# BLDC_driver.net
KiCad netlist of a schematic drawn in Altium Designer
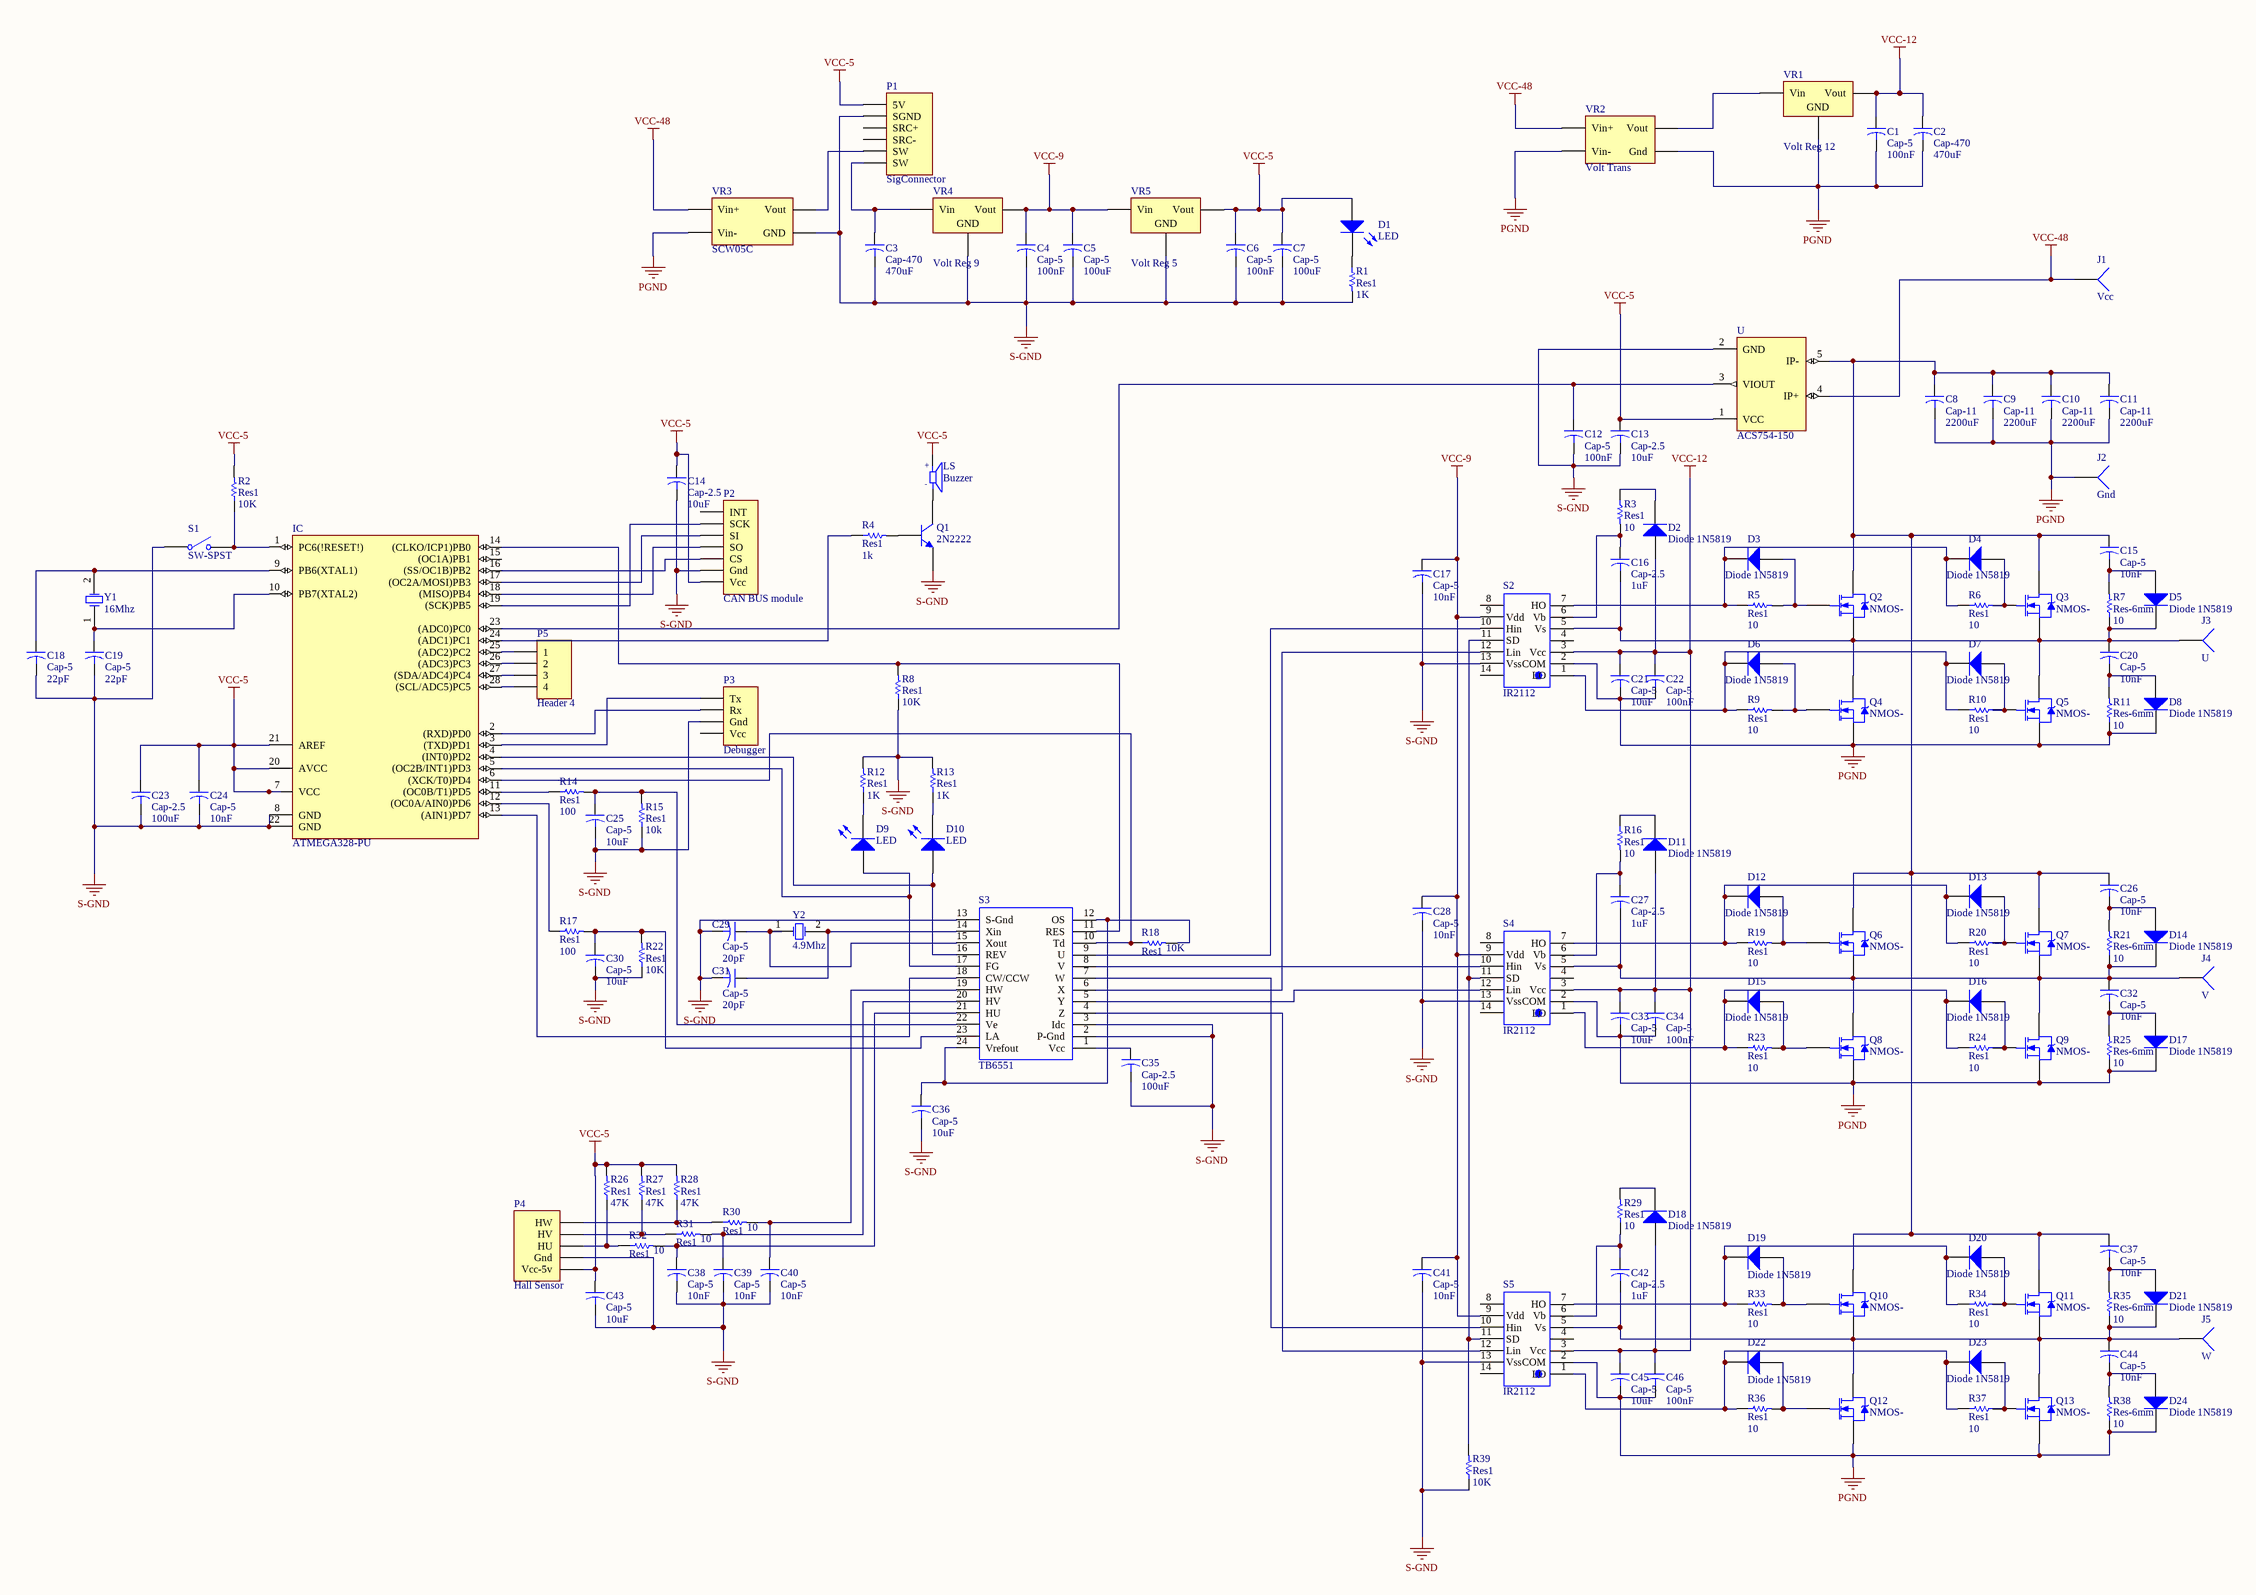
[diagram p0: BLDC_driver.SchDoc]

(export (version "E")
  (design (tool "Eeschema 10.0.6"))
  (components
    (comp (ref "C1")
      (value "Cap-5")
      (footprint "CAP-5mm")
      (description "Capacitor")
      (fields (field (name "ALTIUM_VALUE") "100nF") (field (name "PUBLISHER") "Altium Limited"))
      (libsource (lib "BLDC_driver") (part "Cap-5"))
    )
    (comp (ref "C2")
      (value "Cap-470")
      (footprint "CAP-5-470")
      (description "Capacitor")
      (fields (field (name "ALTIUM_VALUE") "470uF") (field (name "PUBLISHER") "Altium Limited"))
      (libsource (lib "BLDC_driver") (part "Cap-470"))
    )
    (comp (ref "C3")
      (value "Cap-470")
      (footprint "CAP-5-470")
      (description "Capacitor")
      (fields (field (name "ALTIUM_VALUE") "470uF") (field (name "PUBLISHER") "Altium Limited"))
      (libsource (lib "BLDC_driver") (part "Cap-470"))
    )
    (comp (ref "C4")
      (value "Cap-5")
      (footprint "CAP-5mm")
      (description "Capacitor")
      (fields (field (name "ALTIUM_VALUE") "100nF") (field (name "PUBLISHER") "Altium Limited"))
      (libsource (lib "BLDC_driver") (part "Cap-5"))
    )
    (comp (ref "C5")
      (value "Cap-5")
      (footprint "CAP-5mm")
      (description "Capacitor")
      (fields (field (name "ALTIUM_VALUE") "100uF") (field (name "PUBLISHER") "Altium Limited"))
      (libsource (lib "Miscellaneous Devices") (part "Cap-5"))
    )
    (comp (ref "C6")
      (value "Cap-5")
      (footprint "CAP-5mm")
      (description "Capacitor")
      (fields (field (name "ALTIUM_VALUE") "100nF") (field (name "PUBLISHER") "Altium Limited"))
      (libsource (lib "BLDC_driver") (part "Cap-5"))
    )
    (comp (ref "C7")
      (value "Cap-5")
      (footprint "CAP-5mm")
      (description "Capacitor")
      (fields (field (name "ALTIUM_VALUE") "100uF") (field (name "PUBLISHER") "Altium Limited"))
      (libsource (lib "Miscellaneous Devices") (part "Cap-5"))
    )
    (comp (ref "C8")
      (value "Cap-11")
      (footprint "CAP-11mm")
      (description "Capacitor")
      (fields (field (name "ALTIUM_VALUE") "2200uF") (field (name "PUBLISHER") "Altium Limited"))
      (libsource (lib "BLDC_driver") (part "Cap-11"))
    )
    (comp (ref "C9")
      (value "Cap-11")
      (footprint "CAP-11mm")
      (description "Capacitor")
      (fields (field (name "ALTIUM_VALUE") "2200uF") (field (name "PUBLISHER") "Altium Limited"))
      (libsource (lib "BLDC_driver") (part "Cap-11"))
    )
    (comp (ref "C10")
      (value "Cap-11")
      (footprint "CAP-11mm")
      (description "Capacitor")
      (fields (field (name "ALTIUM_VALUE") "2200uF") (field (name "PUBLISHER") "Altium Limited"))
      (libsource (lib "BLDC_driver") (part "Cap-11"))
    )
    (comp (ref "C11")
      (value "Cap-11")
      (footprint "CAP-11mm")
      (description "Capacitor")
      (fields (field (name "ALTIUM_VALUE") "2200uF") (field (name "PUBLISHER") "Altium Limited"))
      (libsource (lib "BLDC_driver") (part "Cap-11"))
    )
    (comp (ref "C12")
      (value "Cap-5")
      (footprint "CAP-5mm")
      (description "Capacitor")
      (fields (field (name "ALTIUM_VALUE") "100nF") (field (name "PUBLISHER") "Altium Limited"))
      (libsource (lib "BLDC_driver") (part "Cap-5"))
    )
    (comp (ref "C13")
      (value "Cap-2.5")
      (footprint "CAP-2.5mm")
      (description "Capacitor")
      (fields (field (name "ALTIUM_VALUE") "10uF") (field (name "PUBLISHER") "Altium Limited"))
      (libsource (lib "BLDC_driver") (part "Cap-2.5"))
    )
    (comp (ref "C14")
      (value "Cap-2.5")
      (footprint "CAP-2.5mm")
      (description "Capacitor")
      (fields (field (name "ALTIUM_VALUE") "10uF") (field (name "PUBLISHER") "Altium Limited"))
      (libsource (lib "BLDC_driver") (part "Cap-2.5"))
    )
    (comp (ref "C15")
      (value "Cap-5")
      (footprint "CAP-5mm")
      (description "Capacitor")
      (fields (field (name "ALTIUM_VALUE") "10nF") (field (name "PUBLISHER") "Altium Limited"))
      (libsource (lib "BLDC_driver") (part "Cap-5"))
    )
    (comp (ref "C16")
      (value "Cap-2.5")
      (footprint "CAP-2.5mm")
      (description "Capacitor")
      (fields (field (name "ALTIUM_VALUE") "1uF") (field (name "PUBLISHER") "Altium Limited"))
      (libsource (lib "BLDC_driver") (part "Cap-2.5"))
    )
    (comp (ref "C17")
      (value "Cap-5")
      (footprint "CAP-5mm")
      (description "Capacitor")
      (fields (field (name "ALTIUM_VALUE") "10nF") (field (name "PUBLISHER") "Altium Limited"))
      (libsource (lib "BLDC_driver") (part "Cap-5"))
    )
    (comp (ref "C18")
      (value "Cap-5")
      (footprint "CAP-5mm")
      (description "Capacitor")
      (fields (field (name "ALTIUM_VALUE") "22pF") (field (name "PUBLISHER") "Altium Limited"))
      (libsource (lib "BLDC_driver") (part "Cap-5"))
    )
    (comp (ref "C19")
      (value "Cap-5")
      (footprint "CAP-5mm")
      (description "Capacitor")
      (fields (field (name "ALTIUM_VALUE") "22pF") (field (name "PUBLISHER") "Altium Limited"))
      (libsource (lib "BLDC_driver") (part "Cap-5"))
    )
    (comp (ref "C20")
      (value "Cap-5")
      (footprint "CAP-5mm")
      (description "Capacitor")
      (fields (field (name "ALTIUM_VALUE") "10nF") (field (name "PUBLISHER") "Altium Limited"))
      (libsource (lib "BLDC_driver") (part "Cap-5"))
    )
    (comp (ref "C21")
      (value "Cap-5")
      (footprint "CAP-5mm")
      (description "Capacitor")
      (fields (field (name "ALTIUM_VALUE") "10uF") (field (name "PUBLISHER") "Altium Limited"))
      (libsource (lib "BLDC_driver") (part "Cap-5"))
    )
    (comp (ref "C22")
      (value "Cap-5")
      (footprint "CAP-5mm")
      (description "Capacitor")
      (fields (field (name "ALTIUM_VALUE") "100nF") (field (name "PUBLISHER") "Altium Limited"))
      (libsource (lib "BLDC_driver") (part "Cap-5"))
    )
    (comp (ref "C23")
      (value "Cap-2.5")
      (footprint "CAP-2.5mm")
      (description "Capacitor")
      (fields (field (name "ALTIUM_VALUE") "100uF") (field (name "PUBLISHER") "Altium Limited"))
      (libsource (lib "BLDC_driver") (part "Cap-2.5"))
    )
    (comp (ref "C24")
      (value "Cap-5")
      (footprint "CAP-5mm")
      (description "Capacitor")
      (fields (field (name "ALTIUM_VALUE") "10nF") (field (name "PUBLISHER") "Altium Limited"))
      (libsource (lib "BLDC_driver") (part "Cap-5"))
    )
    (comp (ref "C25")
      (value "Cap-5")
      (footprint "CAP-5mm")
      (description "Capacitor")
      (fields (field (name "ALTIUM_VALUE") "10uF") (field (name "PUBLISHER") "Altium Limited"))
      (libsource (lib "BLDC_driver") (part "Cap-5"))
    )
    (comp (ref "C26")
      (value "Cap-5")
      (footprint "CAP-5mm")
      (description "Capacitor")
      (fields (field (name "ALTIUM_VALUE") "10nF") (field (name "PUBLISHER") "Altium Limited"))
      (libsource (lib "BLDC_driver") (part "Cap-5"))
    )
    (comp (ref "C27")
      (value "Cap-2.5")
      (footprint "CAP-2.5mm")
      (description "Capacitor")
      (fields (field (name "ALTIUM_VALUE") "1uF") (field (name "PUBLISHER") "Altium Limited"))
      (libsource (lib "BLDC_driver") (part "Cap-2.5"))
    )
    (comp (ref "C28")
      (value "Cap-5")
      (footprint "CAP-5mm")
      (description "Capacitor")
      (fields (field (name "ALTIUM_VALUE") "10nF") (field (name "PUBLISHER") "Altium Limited"))
      (libsource (lib "BLDC_driver") (part "Cap-5"))
    )
    (comp (ref "C29")
      (value "Cap-5")
      (footprint "CAP-5mm")
      (description "Capacitor")
      (fields (field (name "ALTIUM_VALUE") "20pF") (field (name "PUBLISHER") "Altium Limited"))
      (libsource (lib "BLDC_driver") (part "Cap-5"))
    )
    (comp (ref "C30")
      (value "Cap-5")
      (footprint "CAP-5mm")
      (description "Capacitor")
      (fields (field (name "ALTIUM_VALUE") "10uF") (field (name "PUBLISHER") "Altium Limited"))
      (libsource (lib "BLDC_driver") (part "Cap-5"))
    )
    (comp (ref "C31")
      (value "Cap-5")
      (footprint "CAP-5mm")
      (description "Capacitor")
      (fields (field (name "ALTIUM_VALUE") "20pF") (field (name "PUBLISHER") "Altium Limited"))
      (libsource (lib "BLDC_driver") (part "Cap-5"))
    )
    (comp (ref "C32")
      (value "Cap-5")
      (footprint "CAP-5mm")
      (description "Capacitor")
      (fields (field (name "ALTIUM_VALUE") "10nF") (field (name "PUBLISHER") "Altium Limited"))
      (libsource (lib "BLDC_driver") (part "Cap-5"))
    )
    (comp (ref "C33")
      (value "Cap-5")
      (footprint "CAP-5mm")
      (description "Capacitor")
      (fields (field (name "ALTIUM_VALUE") "10uF") (field (name "PUBLISHER") "Altium Limited"))
      (libsource (lib "BLDC_driver") (part "Cap-5"))
    )
    (comp (ref "C34")
      (value "Cap-5")
      (footprint "CAP-5mm")
      (description "Capacitor")
      (fields (field (name "ALTIUM_VALUE") "100nF") (field (name "PUBLISHER") "Altium Limited"))
      (libsource (lib "BLDC_driver") (part "Cap-5"))
    )
    (comp (ref "C35")
      (value "Cap-2.5")
      (footprint "CAP-2.5mm")
      (description "Capacitor")
      (fields (field (name "ALTIUM_VALUE") "100uF") (field (name "PUBLISHER") "Altium Limited"))
      (libsource (lib "BLDC_driver") (part "Cap-2.5"))
    )
    (comp (ref "C36")
      (value "Cap-5")
      (footprint "CAP-5mm")
      (description "Capacitor")
      (fields (field (name "ALTIUM_VALUE") "10uF") (field (name "PUBLISHER") "Altium Limited"))
      (libsource (lib "BLDC_driver") (part "Cap-5"))
    )
    (comp (ref "C37")
      (value "Cap-5")
      (footprint "CAP-5mm")
      (description "Capacitor")
      (fields (field (name "ALTIUM_VALUE") "10nF") (field (name "PUBLISHER") "Altium Limited"))
      (libsource (lib "BLDC_driver") (part "Cap-5"))
    )
    (comp (ref "C38")
      (value "Cap-5")
      (footprint "CAP-5mm")
      (description "Capacitor")
      (fields (field (name "ALTIUM_VALUE") "10nF") (field (name "PUBLISHER") "Altium Limited"))
      (libsource (lib "BLDC_driver") (part "Cap-5"))
    )
    (comp (ref "C39")
      (value "Cap-5")
      (footprint "CAP-5mm")
      (description "Capacitor")
      (fields (field (name "ALTIUM_VALUE") "10nF") (field (name "PUBLISHER") "Altium Limited"))
      (libsource (lib "BLDC_driver") (part "Cap-5"))
    )
    (comp (ref "C40")
      (value "Cap-5")
      (footprint "CAP-5mm")
      (description "Capacitor")
      (fields (field (name "ALTIUM_VALUE") "10nF") (field (name "PUBLISHER") "Altium Limited"))
      (libsource (lib "BLDC_driver") (part "Cap-5"))
    )
    (comp (ref "C41")
      (value "Cap-5")
      (footprint "CAP-5mm")
      (description "Capacitor")
      (fields (field (name "ALTIUM_VALUE") "10nF") (field (name "PUBLISHER") "Altium Limited"))
      (libsource (lib "BLDC_driver") (part "Cap-5"))
    )
    (comp (ref "C42")
      (value "Cap-2.5")
      (footprint "CAP-2.5mm")
      (description "Capacitor")
      (fields (field (name "ALTIUM_VALUE") "1uF") (field (name "PUBLISHER") "Altium Limited"))
      (libsource (lib "BLDC_driver") (part "Cap-2.5"))
    )
    (comp (ref "C43")
      (value "Cap-5")
      (footprint "CAP-5mm")
      (description "Capacitor")
      (fields (field (name "ALTIUM_VALUE") "10uF") (field (name "PUBLISHER") "Altium Limited"))
      (libsource (lib "BLDC_driver") (part "Cap-5"))
    )
    (comp (ref "C44")
      (value "Cap-5")
      (footprint "CAP-5mm")
      (description "Capacitor")
      (fields (field (name "ALTIUM_VALUE") "10nF") (field (name "PUBLISHER") "Altium Limited"))
      (libsource (lib "BLDC_driver") (part "Cap-5"))
    )
    (comp (ref "C45")
      (value "Cap-5")
      (footprint "CAP-5mm")
      (description "Capacitor")
      (fields (field (name "ALTIUM_VALUE") "10uF") (field (name "PUBLISHER") "Altium Limited"))
      (libsource (lib "BLDC_driver") (part "Cap-5"))
    )
    (comp (ref "C46")
      (value "Cap-5")
      (footprint "CAP-5mm")
      (description "Capacitor")
      (fields (field (name "ALTIUM_VALUE") "100nF") (field (name "PUBLISHER") "Altium Limited"))
      (libsource (lib "BLDC_driver") (part "Cap-5"))
    )
    (comp (ref "D1")
      (value "LED")
      (footprint "LED-2.5mm")
      (description "Typical LED")
      (fields (field (name "PUBLISHER") "Altium Limited"))
      (libsource (lib "BLDC_driver") (part "LED0"))
    )
    (comp (ref "D2")
      (value "Diode 1N5819")
      (footprint "DO-5mm")
      (description "3 Amp Medium Power Silicon Rectifier Diode")
      (fields (field (name "PUBLISHER") "Altium Limited"))
      (libsource (lib "BLDC_driver") (part "Diode 1N5408"))
    )
    (comp (ref "D3")
      (value "Diode 1N5819")
      (footprint "DO-5mm")
      (description "3 Amp Medium Power Silicon Rectifier Diode")
      (fields (field (name "PUBLISHER") "Altium Limited"))
      (libsource (lib "BLDC_driver") (part "Diode 1N5408"))
    )
    (comp (ref "D4")
      (value "Diode 1N5819")
      (footprint "DO-5mm")
      (description "3 Amp Medium Power Silicon Rectifier Diode")
      (fields (field (name "PUBLISHER") "Altium Limited"))
      (libsource (lib "BLDC_driver") (part "Diode 1N5408"))
    )
    (comp (ref "D5")
      (value "Diode 1N5819")
      (footprint "DO-5mm")
      (description "3 Amp Medium Power Silicon Rectifier Diode")
      (fields (field (name "PUBLISHER") "Altium Limited"))
      (libsource (lib "BLDC_driver") (part "Diode 1N4001"))
    )
    (comp (ref "D6")
      (value "Diode 1N5819")
      (footprint "DO-5mm")
      (description "3 Amp Medium Power Silicon Rectifier Diode")
      (fields (field (name "PUBLISHER") "Altium Limited"))
      (libsource (lib "BLDC_driver") (part "Diode 1N5408"))
    )
    (comp (ref "D7")
      (value "Diode 1N5819")
      (footprint "DO-5mm")
      (description "3 Amp Medium Power Silicon Rectifier Diode")
      (fields (field (name "PUBLISHER") "Altium Limited"))
      (libsource (lib "BLDC_driver") (part "Diode 1N5408"))
    )
    (comp (ref "D8")
      (value "Diode 1N5819")
      (footprint "DO-5mm")
      (description "3 Amp Medium Power Silicon Rectifier Diode")
      (fields (field (name "PUBLISHER") "Altium Limited"))
      (libsource (lib "BLDC_driver") (part "Diode 1N4001"))
    )
    (comp (ref "D9")
      (value "LED")
      (footprint "LED-2.5mm")
      (description "Typical LED")
      (fields (field (name "PUBLISHER") "Altium Limited"))
      (libsource (lib "BLDC_driver") (part "LED0"))
    )
    (comp (ref "D10")
      (value "LED")
      (footprint "LED-2.5mm")
      (description "Typical LED")
      (fields (field (name "PUBLISHER") "Altium Limited"))
      (libsource (lib "BLDC_driver") (part "LED0"))
    )
    (comp (ref "D11")
      (value "Diode 1N5819")
      (footprint "DO-5mm")
      (description "3 Amp Medium Power Silicon Rectifier Diode")
      (fields (field (name "PUBLISHER") "Altium Limited"))
      (libsource (lib "BLDC_driver") (part "Diode 1N5408"))
    )
    (comp (ref "D12")
      (value "Diode 1N5819")
      (footprint "DO-5mm")
      (description "3 Amp Medium Power Silicon Rectifier Diode")
      (fields (field (name "PUBLISHER") "Altium Limited"))
      (libsource (lib "BLDC_driver") (part "Diode 1N5408"))
    )
    (comp (ref "D13")
      (value "Diode 1N5819")
      (footprint "DO-5mm")
      (description "3 Amp Medium Power Silicon Rectifier Diode")
      (fields (field (name "PUBLISHER") "Altium Limited"))
      (libsource (lib "BLDC_driver") (part "Diode 1N5408"))
    )
    (comp (ref "D14")
      (value "Diode 1N5819")
      (footprint "DO-5mm")
      (description "3 Amp Medium Power Silicon Rectifier Diode")
      (fields (field (name "PUBLISHER") "Altium Limited"))
      (libsource (lib "BLDC_driver") (part "Diode 1N4001"))
    )
    (comp (ref "D15")
      (value "Diode 1N5819")
      (footprint "DO-5mm")
      (description "3 Amp Medium Power Silicon Rectifier Diode")
      (fields (field (name "PUBLISHER") "Altium Limited"))
      (libsource (lib "BLDC_driver") (part "Diode 1N5408"))
    )
    (comp (ref "D16")
      (value "Diode 1N5819")
      (footprint "DO-5mm")
      (description "3 Amp Medium Power Silicon Rectifier Diode")
      (fields (field (name "PUBLISHER") "Altium Limited"))
      (libsource (lib "BLDC_driver") (part "Diode 1N5408"))
    )
    (comp (ref "D17")
      (value "Diode 1N5819")
      (footprint "DO-5mm")
      (description "3 Amp Medium Power Silicon Rectifier Diode")
      (fields (field (name "PUBLISHER") "Altium Limited"))
      (libsource (lib "BLDC_driver") (part "Diode 1N4001"))
    )
    (comp (ref "D18")
      (value "Diode 1N5819")
      (footprint "DO-5mm")
      (description "3 Amp Medium Power Silicon Rectifier Diode")
      (fields (field (name "PUBLISHER") "Altium Limited"))
      (libsource (lib "BLDC_driver") (part "Diode 1N5408"))
    )
    (comp (ref "D19")
      (value "Diode 1N5819")
      (footprint "DO-5mm")
      (description "3 Amp Medium Power Silicon Rectifier Diode")
      (fields (field (name "PUBLISHER") "Altium Limited"))
      (libsource (lib "BLDC_driver") (part "Diode 1N5408"))
    )
    (comp (ref "D20")
      (value "Diode 1N5819")
      (footprint "DO-5mm")
      (description "3 Amp Medium Power Silicon Rectifier Diode")
      (fields (field (name "PUBLISHER") "Altium Limited"))
      (libsource (lib "BLDC_driver") (part "Diode 1N5408"))
    )
    (comp (ref "D21")
      (value "Diode 1N5819")
      (footprint "DO-5mm")
      (description "3 Amp Medium Power Silicon Rectifier Diode")
      (fields (field (name "PUBLISHER") "Altium Limited"))
      (libsource (lib "BLDC_driver") (part "Diode 1N4001"))
    )
    (comp (ref "D22")
      (value "Diode 1N5819")
      (footprint "DO-5mm")
      (description "3 Amp Medium Power Silicon Rectifier Diode")
      (fields (field (name "PUBLISHER") "Altium Limited"))
      (libsource (lib "BLDC_driver") (part "Diode 1N5408"))
    )
    (comp (ref "D23")
      (value "Diode 1N5819")
      (footprint "DO-5mm")
      (description "3 Amp Medium Power Silicon Rectifier Diode")
      (fields (field (name "PUBLISHER") "Altium Limited"))
      (libsource (lib "BLDC_driver") (part "Diode 1N5408"))
    )
    (comp (ref "D24")
      (value "Diode 1N5819")
      (footprint "DO-5mm")
      (description "3 Amp Medium Power Silicon Rectifier Diode")
      (fields (field (name "PUBLISHER") "Altium Limited"))
      (libsource (lib "BLDC_driver") (part "Diode 1N4001"))
    )
    (comp (ref "IC")
      (value "ATMEGA328-PU")
      (footprint "DIL28")
      (description "AVR AVRÂ® ATmega Microcontroller IC 8-Bit 20MHz 32KB _16K x 16_ FLASH 28-PDIP")
      (fields (field (name "MF") "Microchip Technology"))
      (libsource (lib "ATMEGA328-PU") (part "ATMEGA328-PU"))
    )
    (comp (ref "J1")
      (value "Vcc")
      (footprint "Plug-high")
      (description "Socket")
      (fields (field (name "PUBLISHER") "Altium Limited"))
      (libsource (lib "BLDC_driver") (part "Socket"))
    )
    (comp (ref "J2")
      (value "Gnd")
      (footprint "Plug-high")
      (description "Socket")
      (fields (field (name "PUBLISHER") "Altium Limited"))
      (libsource (lib "BLDC_driver") (part "Socket"))
    )
    (comp (ref "J3")
      (value "U")
      (footprint "Plug-high")
      (description "Socket")
      (fields (field (name "PUBLISHER") "Altium Limited"))
      (libsource (lib "BLDC_driver") (part "Socket"))
    )
    (comp (ref "J4")
      (value "V")
      (footprint "Plug-high")
      (description "Socket")
      (fields (field (name "PUBLISHER") "Altium Limited"))
      (libsource (lib "BLDC_driver") (part "Socket"))
    )
    (comp (ref "J5")
      (value "W")
      (footprint "Plug-high")
      (description "Socket")
      (fields (field (name "PUBLISHER") "Altium Limited"))
      (libsource (lib "BLDC_driver") (part "Socket"))
    )
    (comp (ref "LS")
      (value "Buzzer")
      (footprint "CUI_CEM-1201(42)")
      (description "Buzzer, 12 mm, 1,5 V, 85 dB")
      (fields (field (name "MF") "CUI Devices") (field (name "MP") "CEM-1201_42_"))
      (libsource (lib "BLDC_driver") (part "Buzzer"))
    )
    (comp (ref "P1")
      (value "SigConnector")
      (footprint "Sig Connector")
      (description "Header, 6-Pin")
      (fields (field (name "PUBLISHER") "Altium Limited"))
      (libsource (lib "BLDC_driver") (part "SigConnector"))
    )
    (comp (ref "P2")
      (value "CAN BUS module")
      (footprint "HDR1X7")
      (description "Header, 7-Pin")
      (fields (field (name "PUBLISHER") "Altium Limited"))
      (libsource (lib "BLDC_driver") (part "CAN BUS module"))
    )
    (comp (ref "P3")
      (value "Debugger")
      (footprint "HDR1X4")
      (description "Header, 4-Pin")
      (fields (field (name "PUBLISHER") "Altium Limited"))
      (libsource (lib "BLDC_driver") (part "Debugger"))
    )
    (comp (ref "P4")
      (value "Hall Sensor")
      (footprint "Header-5")
      (description "Header, 5-Pin")
      (fields (field (name "PUBLISHER") "Altium Limited"))
      (libsource (lib "BLDC_driver") (part "Hall Sensor"))
    )
    (comp (ref "P5")
      (value "Header 4")
      (footprint "HDR1X4")
      (description "Header, 4-Pin")
      (fields (field (name "PUBLISHER") "Altium Limited"))
      (libsource (lib "Miscellaneous Connectors") (part "Header 4"))
    )
    (comp (ref "Q1")
      (value "2N2222")
      (footprint "TO-92A")
      (description "NPN General Purpose Amplifier")
      (fields (field (name "PUBLISHER") "Altium Limited"))
      (libsource (lib "BLDC_driver") (part "2N2222"))
    )
    (comp (ref "Q2")
      (value "NMOS-")
      (footprint "TO-220AB")
      (description "IRFB4110")
      (fields (field (name "PUBLISHER") "Altium Limited"))
      (libsource (lib "BLDC_driver") (part "NMOS-"))
    )
    (comp (ref "Q3")
      (value "NMOS-")
      (footprint "TO-220AB")
      (description "IRFB4110")
      (fields (field (name "PUBLISHER") "Altium Limited"))
      (libsource (lib "BLDC_driver") (part "NMOS-"))
    )
    (comp (ref "Q4")
      (value "NMOS-")
      (footprint "TO-220AB")
      (description "IRFB4110")
      (fields (field (name "PUBLISHER") "Altium Limited"))
      (libsource (lib "BLDC_driver") (part "NMOS-"))
    )
    (comp (ref "Q5")
      (value "NMOS-")
      (footprint "TO-220AB")
      (description "IRFB4110")
      (fields (field (name "PUBLISHER") "Altium Limited"))
      (libsource (lib "BLDC_driver") (part "NMOS-"))
    )
    (comp (ref "Q6")
      (value "NMOS-")
      (footprint "TO-220AB")
      (description "IRFB4110")
      (fields (field (name "PUBLISHER") "Altium Limited"))
      (libsource (lib "BLDC_driver") (part "NMOS-"))
    )
    (comp (ref "Q7")
      (value "NMOS-")
      (footprint "TO-220AB")
      (description "IRFB4110")
      (fields (field (name "PUBLISHER") "Altium Limited"))
      (libsource (lib "BLDC_driver") (part "NMOS-"))
    )
    (comp (ref "Q8")
      (value "NMOS-")
      (footprint "TO-220AB")
      (description "IRFB4110")
      (fields (field (name "PUBLISHER") "Altium Limited"))
      (libsource (lib "BLDC_driver") (part "NMOS-"))
    )
    (comp (ref "Q9")
      (value "NMOS-")
      (footprint "TO-220AB")
      (description "IRFB4110")
      (fields (field (name "PUBLISHER") "Altium Limited"))
      (libsource (lib "BLDC_driver") (part "NMOS-"))
    )
    (comp (ref "Q10")
      (value "NMOS-")
      (footprint "TO-220AB")
      (description "IRFB4110")
      (fields (field (name "PUBLISHER") "Altium Limited"))
      (libsource (lib "BLDC_driver") (part "NMOS-"))
    )
    (comp (ref "Q11")
      (value "NMOS-")
      (footprint "TO-220AB")
      (description "IRFB4110")
      (fields (field (name "PUBLISHER") "Altium Limited"))
      (libsource (lib "BLDC_driver") (part "NMOS-"))
    )
    (comp (ref "Q12")
      (value "NMOS-")
      (footprint "TO-220AB")
      (description "IRFB4110")
      (fields (field (name "PUBLISHER") "Altium Limited"))
      (libsource (lib "BLDC_driver") (part "NMOS-"))
    )
    (comp (ref "Q13")
      (value "NMOS-")
      (footprint "TO-220AB")
      (description "IRFB4110")
      (fields (field (name "PUBLISHER") "Altium Limited"))
      (libsource (lib "BLDC_driver") (part "NMOS-"))
    )
    (comp (ref "R1")
      (value "Res1")
      (footprint "AXIAL-5mm")
      (description "Resistor")
      (fields (field (name "ALTIUM_VALUE") "1K") (field (name "PUBLISHER") "Altium Limited"))
      (libsource (lib "BLDC_driver") (part "Res1"))
    )
    (comp (ref "R2")
      (value "Res1")
      (footprint "AXIAL-5mm")
      (description "Resistor")
      (fields (field (name "ALTIUM_VALUE") "10K") (field (name "PUBLISHER") "Altium Limited"))
      (libsource (lib "BLDC_driver") (part "Res1"))
    )
    (comp (ref "R3")
      (value "Res1")
      (footprint "AXIAL-5mm")
      (description "Resistor")
      (fields (field (name "ALTIUM_VALUE") "10") (field (name "PUBLISHER") "Altium Limited"))
      (libsource (lib "BLDC_driver") (part "Res1"))
    )
    (comp (ref "R4")
      (value "Res1")
      (footprint "AXIAL-5mm")
      (description "Resistor")
      (fields (field (name "ALTIUM_VALUE") "1k") (field (name "PUBLISHER") "Altium Limited"))
      (libsource (lib "BLDC_driver") (part "Res1"))
    )
    (comp (ref "R5")
      (value "Res1")
      (footprint "AXIAL-5mm")
      (description "Resistor")
      (fields (field (name "ALTIUM_VALUE") "10") (field (name "PUBLISHER") "Altium Limited"))
      (libsource (lib "BLDC_driver") (part "Res1"))
    )
    (comp (ref "R6")
      (value "Res1")
      (footprint "AXIAL-5mm")
      (description "Resistor")
      (fields (field (name "ALTIUM_VALUE") "10") (field (name "PUBLISHER") "Altium Limited"))
      (libsource (lib "BLDC_driver") (part "Res1"))
    )
    (comp (ref "R7")
      (value "Res-6mm")
      (footprint "DO-6mm")
      (description "Resistor")
      (fields (field (name "ALTIUM_VALUE") "10") (field (name "PUBLISHER") "Altium Limited"))
      (libsource (lib "BLDC_driver") (part "Res-6mm"))
    )
    (comp (ref "R8")
      (value "Res1")
      (footprint "AXIAL-5mm")
      (description "Resistor")
      (fields (field (name "ALTIUM_VALUE") "10K") (field (name "PUBLISHER") "Altium Limited"))
      (libsource (lib "BLDC_driver") (part "Res1"))
    )
    (comp (ref "R9")
      (value "Res1")
      (footprint "AXIAL-5mm")
      (description "Resistor")
      (fields (field (name "ALTIUM_VALUE") "10") (field (name "PUBLISHER") "Altium Limited"))
      (libsource (lib "BLDC_driver") (part "Res1"))
    )
    (comp (ref "R10")
      (value "Res1")
      (footprint "AXIAL-5mm")
      (description "Resistor")
      (fields (field (name "ALTIUM_VALUE") "10") (field (name "PUBLISHER") "Altium Limited"))
      (libsource (lib "BLDC_driver") (part "Res1"))
    )
    (comp (ref "R11")
      (value "Res-6mm")
      (footprint "DO-6mm")
      (description "Resistor")
      (fields (field (name "ALTIUM_VALUE") "10") (field (name "PUBLISHER") "Altium Limited"))
      (libsource (lib "BLDC_driver") (part "Res-6mm"))
    )
    (comp (ref "R12")
      (value "Res1")
      (footprint "AXIAL-5mm")
      (description "Resistor")
      (fields (field (name "ALTIUM_VALUE") "1K") (field (name "PUBLISHER") "Altium Limited"))
      (libsource (lib "BLDC_driver") (part "Res1"))
    )
    (comp (ref "R13")
      (value "Res1")
      (footprint "AXIAL-5mm")
      (description "Resistor")
      (fields (field (name "ALTIUM_VALUE") "1K") (field (name "PUBLISHER") "Altium Limited"))
      (libsource (lib "BLDC_driver") (part "Res1"))
    )
    (comp (ref "R14")
      (value "Res1")
      (footprint "AXIAL-5mm")
      (description "Resistor")
      (fields (field (name "ALTIUM_VALUE") "100") (field (name "PUBLISHER") "Altium Limited"))
      (libsource (lib "BLDC_driver") (part "Res1"))
    )
    (comp (ref "R15")
      (value "Res1")
      (footprint "AXIAL-5mm")
      (description "Resistor")
      (fields (field (name "ALTIUM_VALUE") "10k") (field (name "PUBLISHER") "Altium Limited"))
      (libsource (lib "BLDC_driver") (part "Res1"))
    )
    (comp (ref "R16")
      (value "Res1")
      (footprint "AXIAL-5mm")
      (description "Resistor")
      (fields (field (name "ALTIUM_VALUE") "10") (field (name "PUBLISHER") "Altium Limited"))
      (libsource (lib "BLDC_driver") (part "Res1"))
    )
    (comp (ref "R17")
      (value "Res1")
      (footprint "AXIAL-5mm")
      (description "Resistor")
      (fields (field (name "ALTIUM_VALUE") "100") (field (name "PUBLISHER") "Altium Limited"))
      (libsource (lib "BLDC_driver") (part "Res1"))
    )
    (comp (ref "R18")
      (value "Res1")
      (footprint "AXIAL-5mm")
      (description "Resistor")
      (fields (field (name "ALTIUM_VALUE") "10K") (field (name "PUBLISHER") "Altium Limited"))
      (libsource (lib "BLDC_driver") (part "Res1"))
    )
    (comp (ref "R19")
      (value "Res1")
      (footprint "AXIAL-5mm")
      (description "Resistor")
      (fields (field (name "ALTIUM_VALUE") "10") (field (name "PUBLISHER") "Altium Limited"))
      (libsource (lib "BLDC_driver") (part "Res1"))
    )
    (comp (ref "R20")
      (value "Res1")
      (footprint "AXIAL-5mm")
      (description "Resistor")
      (fields (field (name "ALTIUM_VALUE") "10") (field (name "PUBLISHER") "Altium Limited"))
      (libsource (lib "BLDC_driver") (part "Res1"))
    )
    (comp (ref "R21")
      (value "Res-6mm")
      (footprint "DO-6mm")
      (description "Resistor")
      (fields (field (name "ALTIUM_VALUE") "10") (field (name "PUBLISHER") "Altium Limited"))
      (libsource (lib "BLDC_driver") (part "Res-6mm"))
    )
    (comp (ref "R22")
      (value "Res1")
      (footprint "AXIAL-5mm")
      (description "Resistor")
      (fields (field (name "ALTIUM_VALUE") "10K") (field (name "PUBLISHER") "Altium Limited"))
      (libsource (lib "BLDC_driver") (part "Res1"))
    )
    (comp (ref "R23")
      (value "Res1")
      (footprint "AXIAL-5mm")
      (description "Resistor")
      (fields (field (name "ALTIUM_VALUE") "10") (field (name "PUBLISHER") "Altium Limited"))
      (libsource (lib "BLDC_driver") (part "Res1"))
    )
    (comp (ref "R24")
      (value "Res1")
      (footprint "AXIAL-5mm")
      (description "Resistor")
      (fields (field (name "ALTIUM_VALUE") "10") (field (name "PUBLISHER") "Altium Limited"))
      (libsource (lib "BLDC_driver") (part "Res1"))
    )
    (comp (ref "R25")
      (value "Res-6mm")
      (footprint "DO-6mm")
      (description "Resistor")
      (fields (field (name "ALTIUM_VALUE") "10") (field (name "PUBLISHER") "Altium Limited"))
      (libsource (lib "BLDC_driver") (part "Res-6mm"))
    )
    (comp (ref "R26")
      (value "Res1")
      (footprint "AXIAL-5mm")
      (description "Resistor")
      (fields (field (name "ALTIUM_VALUE") "47K") (field (name "PUBLISHER") "Altium Limited"))
      (libsource (lib "BLDC_driver") (part "Res1"))
    )
    (comp (ref "R27")
      (value "Res1")
      (footprint "AXIAL-5mm")
      (description "Resistor")
      (fields (field (name "ALTIUM_VALUE") "47K") (field (name "PUBLISHER") "Altium Limited"))
      (libsource (lib "BLDC_driver") (part "Res1"))
    )
    (comp (ref "R28")
      (value "Res1")
      (footprint "AXIAL-5mm")
      (description "Resistor")
      (fields (field (name "ALTIUM_VALUE") "47K") (field (name "PUBLISHER") "Altium Limited"))
      (libsource (lib "BLDC_driver") (part "Res1"))
    )
    (comp (ref "R29")
      (value "Res1")
      (footprint "AXIAL-5mm")
      (description "Resistor")
      (fields (field (name "ALTIUM_VALUE") "10") (field (name "PUBLISHER") "Altium Limited"))
      (libsource (lib "BLDC_driver") (part "Res1"))
    )
    (comp (ref "R30")
      (value "Res1")
      (footprint "AXIAL-5mm")
      (description "Resistor")
      (fields (field (name "ALTIUM_VALUE") "10") (field (name "PUBLISHER") "Altium Limited"))
      (libsource (lib "BLDC_driver") (part "Res1"))
    )
    (comp (ref "R31")
      (value "Res1")
      (footprint "AXIAL-5mm")
      (description "Resistor")
      (fields (field (name "ALTIUM_VALUE") "10") (field (name "PUBLISHER") "Altium Limited"))
      (libsource (lib "BLDC_driver") (part "Res1"))
    )
    (comp (ref "R32")
      (value "Res1")
      (footprint "AXIAL-5mm")
      (description "Resistor")
      (fields (field (name "ALTIUM_VALUE") "10") (field (name "PUBLISHER") "Altium Limited"))
      (libsource (lib "BLDC_driver") (part "Res1"))
    )
    (comp (ref "R33")
      (value "Res1")
      (footprint "AXIAL-5mm")
      (description "Resistor")
      (fields (field (name "ALTIUM_VALUE") "10") (field (name "PUBLISHER") "Altium Limited"))
      (libsource (lib "BLDC_driver") (part "Res1"))
    )
    (comp (ref "R34")
      (value "Res1")
      (footprint "AXIAL-5mm")
      (description "Resistor")
      (fields (field (name "ALTIUM_VALUE") "10") (field (name "PUBLISHER") "Altium Limited"))
      (libsource (lib "BLDC_driver") (part "Res1"))
    )
    (comp (ref "R35")
      (value "Res-6mm")
      (footprint "DO-6mm")
      (description "Resistor")
      (fields (field (name "ALTIUM_VALUE") "10") (field (name "PUBLISHER") "Altium Limited"))
      (libsource (lib "BLDC_driver") (part "Res-6mm"))
    )
    (comp (ref "R36")
      (value "Res1")
      (footprint "AXIAL-5mm")
      (description "Resistor")
      (fields (field (name "ALTIUM_VALUE") "10") (field (name "PUBLISHER") "Altium Limited"))
      (libsource (lib "BLDC_driver") (part "Res1"))
    )
    (comp (ref "R37")
      (value "Res1")
      (footprint "AXIAL-5mm")
      (description "Resistor")
      (fields (field (name "ALTIUM_VALUE") "10") (field (name "PUBLISHER") "Altium Limited"))
      (libsource (lib "BLDC_driver") (part "Res1"))
    )
    (comp (ref "R38")
      (value "Res-6mm")
      (footprint "DO-6mm")
      (description "Resistor")
      (fields (field (name "ALTIUM_VALUE") "10") (field (name "PUBLISHER") "Altium Limited"))
      (libsource (lib "BLDC_driver") (part "Res-6mm"))
    )
    (comp (ref "R39")
      (value "Res1")
      (footprint "AXIAL-5mm")
      (description "Resistor")
      (fields (field (name "ALTIUM_VALUE") "10K") (field (name "PUBLISHER") "Altium Limited"))
      (libsource (lib "BLDC_driver") (part "Res1"))
    )
    (comp (ref "S1")
      (value "SW-SPST")
      (footprint "SPST-2")
      (description "Single-Pole, Single-Throw Switch")
      (fields (field (name "PUBLISHER") "Altium Limited"))
      (libsource (lib "BLDC_driver") (part "SW-SPST"))
    )
    (comp (ref "S2")
      (value "IR2112")
      (footprint "DIP-14")
      (description "DIP Switch, 7 Position, SPST")
      (fields (field (name "PUBLISHER") "Altium Limited"))
      (libsource (lib "BLDC_driver") (part "SW DIP-7"))
    )
    (comp (ref "S3")
      (value "TB6551")
      (footprint "DIP12")
      (description "DIP Switch, 8 Position, SPST")
      (fields (field (name "PUBLISHER") "Altium Limited"))
      (libsource (lib "BLDC_driver") (part "TB6551"))
    )
    (comp (ref "S4")
      (value "IR2112")
      (footprint "DIP-14")
      (description "DIP Switch, 7 Position, SPST")
      (fields (field (name "PUBLISHER") "Altium Limited"))
      (libsource (lib "BLDC_driver") (part "SW DIP-7"))
    )
    (comp (ref "S5")
      (value "IR2112")
      (footprint "DIP-14")
      (description "DIP Switch, 7 Position, SPST")
      (fields (field (name "PUBLISHER") "Altium Limited"))
      (libsource (lib "BLDC_driver") (part "SW DIP-7"))
    )
    (comp (ref "U")
      (value "ACS754-150")
      (footprint "ACS754-150")
      (description "Current Sensor 50A 1 Channel Hall Effect, Open Loop Unidirectional 5-CB Formed Leads, PFF")
      (fields (field (name "MP") "ACS758") (field (name "MF") "Allegro MicroSystems LLC"))
      (libsource (lib "BLDC_driver") (part "ACS754-150"))
    )
    (comp (ref "VR1")
      (value "Volt Reg 12")
      (footprint "TO-220AB")
      (description "Voltage Regulator")
      (fields (field (name "PUBLISHER") "Altium Limited"))
      (libsource (lib "BLDC_driver") (part "Volt Reg 12"))
    )
    (comp (ref "VR2")
      (value "Volt Trans")
      (footprint "Volt Trans")
      (description "Voltage Regulator")
      (fields (field (name "PUBLISHER") "Altium Limited"))
      (libsource (lib "BLDC_driver") (part "Volt Trans"))
    )
    (comp (ref "VR3")
      (value "SCW05C")
      (footprint "KLD-0202")
      (description "Voltage Regulator")
      (fields (field (name "PUBLISHER") "Altium Limited"))
      (libsource (lib "BLDC_driver") (part "SCW05C"))
    )
    (comp (ref "VR4")
      (value "Volt Reg 9")
      (footprint "TO-220AB")
      (description "Voltage Regulator")
      (fields (field (name "PUBLISHER") "Altium Limited"))
      (libsource (lib "BLDC_driver") (part "Volt Reg 9"))
    )
    (comp (ref "VR5")
      (value "Volt Reg 5")
      (footprint "TO-220AB")
      (description "Voltage Regulator")
      (fields (field (name "PUBLISHER") "Altium Limited"))
      (libsource (lib "BLDC_driver") (part "Volt Reg 5"))
    )
    (comp (ref "Y1")
      (value "16Mhz")
      (footprint "XTAL")
      (description "Crystal Oscillator")
      (fields (field (name "PUBLISHER") "Altium Limited"))
      (libsource (lib "BLDC_driver") (part "XTAL"))
    )
    (comp (ref "Y2")
      (value "4.9Mhz")
      (footprint "XTAL")
      (description "Crystal Oscillator")
      (fields (field (name "PUBLISHER") "Altium Limited"))
      (libsource (lib "Miscellaneous Devices") (part "XTAL"))
    )
  )
  (nets
    (net (code "1") (name "Net-(D1-K)") (class "Default")
      (node (ref "D1") (pin "2") (pinfunction "K_2") (pintype "passive"))
      (node (ref "R1") (pin "1") (pinfunction "1_1") (pintype "passive"))
    )
    (net (code "2") (name "Net-(D2-K)") (class "Default")
      (node (ref "D2") (pin "2") (pinfunction "K_2") (pintype "passive"))
      (node (ref "R3") (pin "1") (pinfunction "1_1") (pintype "passive"))
    )
    (net (code "3") (name "Net-(D3-A)") (class "Default")
      (node (ref "D3") (pin "1") (pinfunction "A_1") (pintype "passive"))
      (node (ref "Q2") (pin "1") (pinfunction "G_1") (pintype "passive"))
      (node (ref "R5") (pin "2") (pinfunction "2_2") (pintype "passive"))
    )
    (net (code "4") (name "Net-(D3-K)") (class "Default")
      (node (ref "D3") (pin "2") (pinfunction "K_2") (pintype "passive"))
      (node (ref "D4") (pin "2") (pinfunction "K_2") (pintype "passive"))
      (node (ref "R5") (pin "1") (pinfunction "1_1") (pintype "passive"))
      (node (ref "R6") (pin "1") (pinfunction "1_1") (pintype "passive"))
      (node (ref "S2") (pin "7") (pinfunction "HO_7") (pintype "passive"))
    )
    (net (code "5") (name "Net-(D4-A)") (class "Default")
      (node (ref "D4") (pin "1") (pinfunction "A_1") (pintype "passive"))
      (node (ref "Q3") (pin "1") (pinfunction "G_1") (pintype "passive"))
      (node (ref "R6") (pin "2") (pinfunction "2_2") (pintype "passive"))
    )
    (net (code "6") (name "Net-(D5-A)") (class "Default")
      (node (ref "C15") (pin "2") (pinfunction "2_2") (pintype "passive"))
      (node (ref "D5") (pin "1") (pinfunction "A_1") (pintype "passive"))
      (node (ref "R7") (pin "2") (pinfunction "2_2") (pintype "passive"))
    )
    (net (code "7") (name "Net-(D5-K)") (class "Default")
      (node (ref "C16") (pin "2") (pinfunction "2_2") (pintype "passive"))
      (node (ref "C20") (pin "1") (pinfunction "1_1") (pintype "passive"))
      (node (ref "D5") (pin "2") (pinfunction "K_2") (pintype "passive"))
      (node (ref "J3") (pin "1") (pinfunction "1_1") (pintype "passive"))
      (node (ref "Q2") (pin "3") (pinfunction "S_3") (pintype "passive"))
      (node (ref "Q3") (pin "3") (pinfunction "S_3") (pintype "passive"))
      (node (ref "Q4") (pin "2") (pinfunction "D_2") (pintype "passive"))
      (node (ref "Q5") (pin "2") (pinfunction "D_2") (pintype "passive"))
      (node (ref "R7") (pin "1") (pinfunction "1_1") (pintype "passive"))
      (node (ref "S2") (pin "5") (pinfunction "Vs_5") (pintype "passive"))
    )
    (net (code "8") (name "Net-(D6-A)") (class "Default")
      (node (ref "D6") (pin "1") (pinfunction "A_1") (pintype "passive"))
      (node (ref "Q4") (pin "1") (pinfunction "G_1") (pintype "passive"))
      (node (ref "R9") (pin "2") (pinfunction "2_2") (pintype "passive"))
    )
    (net (code "9") (name "Net-(D6-K)") (class "Default")
      (node (ref "D6") (pin "2") (pinfunction "K_2") (pintype "passive"))
      (node (ref "D7") (pin "2") (pinfunction "K_2") (pintype "passive"))
      (node (ref "R10") (pin "1") (pinfunction "1_1") (pintype "passive"))
      (node (ref "R9") (pin "1") (pinfunction "1_1") (pintype "passive"))
      (node (ref "S2") (pin "1") (pinfunction "LO_1") (pintype "passive"))
    )
    (net (code "10") (name "Net-(D7-A)") (class "Default")
      (node (ref "D7") (pin "1") (pinfunction "A_1") (pintype "passive"))
      (node (ref "Q5") (pin "1") (pinfunction "G_1") (pintype "passive"))
      (node (ref "R10") (pin "2") (pinfunction "2_2") (pintype "passive"))
    )
    (net (code "11") (name "Net-(D8-A)") (class "Default")
      (node (ref "C20") (pin "2") (pinfunction "2_2") (pintype "passive"))
      (node (ref "D8") (pin "1") (pinfunction "A_1") (pintype "passive"))
      (node (ref "R11") (pin "2") (pinfunction "2_2") (pintype "passive"))
    )
    (net (code "12") (name "Net-(D9-A)") (class "Default")
      (node (ref "D9") (pin "1") (pinfunction "A_1") (pintype "passive"))
      (node (ref "IC") (pin "5") (pinfunction "(OC2B/INT1)PD3_5") (pintype "bidirectional"))
      (node (ref "S3") (pin "17") (pinfunction "FG_17") (pintype "passive"))
    )
    (net (code "13") (name "Net-(D9-K)") (class "Default")
      (node (ref "D9") (pin "2") (pinfunction "K_2") (pintype "passive"))
      (node (ref "R12") (pin "1") (pinfunction "1_1") (pintype "passive"))
    )
    (net (code "14") (name "Net-(D10-A)") (class "Default")
      (node (ref "D10") (pin "1") (pinfunction "A_1") (pintype "passive"))
      (node (ref "IC") (pin "4") (pinfunction "(INT0)PD2_4") (pintype "bidirectional"))
      (node (ref "S3") (pin "16") (pinfunction "REV_16") (pintype "passive"))
    )
    (net (code "15") (name "Net-(D10-K)") (class "Default")
      (node (ref "D10") (pin "2") (pinfunction "K_2") (pintype "passive"))
      (node (ref "R13") (pin "1") (pinfunction "1_1") (pintype "passive"))
    )
    (net (code "16") (name "Net-(D11-K)") (class "Default")
      (node (ref "D11") (pin "2") (pinfunction "K_2") (pintype "passive"))
      (node (ref "R16") (pin "1") (pinfunction "1_1") (pintype "passive"))
    )
    (net (code "17") (name "Net-(D12-A)") (class "Default")
      (node (ref "D12") (pin "1") (pinfunction "A_1") (pintype "passive"))
      (node (ref "Q6") (pin "1") (pinfunction "G_1") (pintype "passive"))
      (node (ref "R19") (pin "2") (pinfunction "2_2") (pintype "passive"))
    )
    (net (code "18") (name "Net-(D12-K)") (class "Default")
      (node (ref "D12") (pin "2") (pinfunction "K_2") (pintype "passive"))
      (node (ref "D13") (pin "2") (pinfunction "K_2") (pintype "passive"))
      (node (ref "R19") (pin "1") (pinfunction "1_1") (pintype "passive"))
      (node (ref "R20") (pin "1") (pinfunction "1_1") (pintype "passive"))
      (node (ref "S4") (pin "7") (pinfunction "HO_7") (pintype "passive"))
    )
    (net (code "19") (name "Net-(D13-A)") (class "Default")
      (node (ref "D13") (pin "1") (pinfunction "A_1") (pintype "passive"))
      (node (ref "Q7") (pin "1") (pinfunction "G_1") (pintype "passive"))
      (node (ref "R20") (pin "2") (pinfunction "2_2") (pintype "passive"))
    )
    (net (code "20") (name "Net-(D14-A)") (class "Default")
      (node (ref "C26") (pin "2") (pinfunction "2_2") (pintype "passive"))
      (node (ref "D14") (pin "1") (pinfunction "A_1") (pintype "passive"))
      (node (ref "R21") (pin "2") (pinfunction "2_2") (pintype "passive"))
    )
    (net (code "21") (name "Net-(D14-K)") (class "Default")
      (node (ref "C27") (pin "2") (pinfunction "2_2") (pintype "passive"))
      (node (ref "C32") (pin "1") (pinfunction "1_1") (pintype "passive"))
      (node (ref "D14") (pin "2") (pinfunction "K_2") (pintype "passive"))
      (node (ref "J4") (pin "1") (pinfunction "1_1") (pintype "passive"))
      (node (ref "Q6") (pin "3") (pinfunction "S_3") (pintype "passive"))
      (node (ref "Q7") (pin "3") (pinfunction "S_3") (pintype "passive"))
      (node (ref "Q8") (pin "2") (pinfunction "D_2") (pintype "passive"))
      (node (ref "Q9") (pin "2") (pinfunction "D_2") (pintype "passive"))
      (node (ref "R21") (pin "1") (pinfunction "1_1") (pintype "passive"))
      (node (ref "S4") (pin "5") (pinfunction "Vs_5") (pintype "passive"))
    )
    (net (code "22") (name "Net-(D15-A)") (class "Default")
      (node (ref "D15") (pin "1") (pinfunction "A_1") (pintype "passive"))
      (node (ref "Q8") (pin "1") (pinfunction "G_1") (pintype "passive"))
      (node (ref "R23") (pin "2") (pinfunction "2_2") (pintype "passive"))
    )
    (net (code "23") (name "Net-(D15-K)") (class "Default")
      (node (ref "D15") (pin "2") (pinfunction "K_2") (pintype "passive"))
      (node (ref "D16") (pin "2") (pinfunction "K_2") (pintype "passive"))
      (node (ref "R23") (pin "1") (pinfunction "1_1") (pintype "passive"))
      (node (ref "R24") (pin "1") (pinfunction "1_1") (pintype "passive"))
      (node (ref "S4") (pin "1") (pinfunction "LO_1") (pintype "passive"))
    )
    (net (code "24") (name "Net-(D16-A)") (class "Default")
      (node (ref "D16") (pin "1") (pinfunction "A_1") (pintype "passive"))
      (node (ref "Q9") (pin "1") (pinfunction "G_1") (pintype "passive"))
      (node (ref "R24") (pin "2") (pinfunction "2_2") (pintype "passive"))
    )
    (net (code "25") (name "Net-(D17-A)") (class "Default")
      (node (ref "C32") (pin "2") (pinfunction "2_2") (pintype "passive"))
      (node (ref "D17") (pin "1") (pinfunction "A_1") (pintype "passive"))
      (node (ref "R25") (pin "2") (pinfunction "2_2") (pintype "passive"))
    )
    (net (code "26") (name "Net-(D18-K)") (class "Default")
      (node (ref "D18") (pin "2") (pinfunction "K_2") (pintype "passive"))
      (node (ref "R29") (pin "2") (pinfunction "2_2") (pintype "passive"))
    )
    (net (code "27") (name "Net-(D19-A)") (class "Default")
      (node (ref "D19") (pin "1") (pinfunction "A_1") (pintype "passive"))
      (node (ref "Q10") (pin "1") (pinfunction "G_1") (pintype "passive"))
      (node (ref "R33") (pin "2") (pinfunction "2_2") (pintype "passive"))
    )
    (net (code "28") (name "Net-(D19-K)") (class "Default")
      (node (ref "D19") (pin "2") (pinfunction "K_2") (pintype "passive"))
      (node (ref "D20") (pin "2") (pinfunction "K_2") (pintype "passive"))
      (node (ref "R33") (pin "1") (pinfunction "1_1") (pintype "passive"))
      (node (ref "R34") (pin "1") (pinfunction "1_1") (pintype "passive"))
      (node (ref "S5") (pin "7") (pinfunction "HO_7") (pintype "passive"))
    )
    (net (code "29") (name "Net-(D20-A)") (class "Default")
      (node (ref "D20") (pin "1") (pinfunction "A_1") (pintype "passive"))
      (node (ref "Q11") (pin "1") (pinfunction "G_1") (pintype "passive"))
      (node (ref "R34") (pin "2") (pinfunction "2_2") (pintype "passive"))
    )
    (net (code "30") (name "Net-(D21-A)") (class "Default")
      (node (ref "C37") (pin "2") (pinfunction "2_2") (pintype "passive"))
      (node (ref "D21") (pin "1") (pinfunction "A_1") (pintype "passive"))
      (node (ref "R35") (pin "2") (pinfunction "2_2") (pintype "passive"))
    )
    (net (code "31") (name "Net-(D21-K)") (class "Default")
      (node (ref "C42") (pin "2") (pinfunction "2_2") (pintype "passive"))
      (node (ref "C44") (pin "1") (pinfunction "1_1") (pintype "passive"))
      (node (ref "D21") (pin "2") (pinfunction "K_2") (pintype "passive"))
      (node (ref "J5") (pin "1") (pinfunction "1_1") (pintype "passive"))
      (node (ref "Q10") (pin "3") (pinfunction "S_3") (pintype "passive"))
      (node (ref "Q11") (pin "3") (pinfunction "S_3") (pintype "passive"))
      (node (ref "Q12") (pin "2") (pinfunction "D_2") (pintype "passive"))
      (node (ref "Q13") (pin "2") (pinfunction "D_2") (pintype "passive"))
      (node (ref "R35") (pin "1") (pinfunction "1_1") (pintype "passive"))
      (node (ref "S5") (pin "5") (pinfunction "Vs_5") (pintype "passive"))
    )
    (net (code "32") (name "Net-(D22-A)") (class "Default")
      (node (ref "D22") (pin "1") (pinfunction "A_1") (pintype "passive"))
      (node (ref "Q12") (pin "1") (pinfunction "G_1") (pintype "passive"))
      (node (ref "R36") (pin "2") (pinfunction "2_2") (pintype "passive"))
    )
    (net (code "33") (name "Net-(D22-K)") (class "Default")
      (node (ref "D22") (pin "2") (pinfunction "K_2") (pintype "passive"))
      (node (ref "D23") (pin "2") (pinfunction "K_2") (pintype "passive"))
      (node (ref "R36") (pin "1") (pinfunction "1_1") (pintype "passive"))
      (node (ref "R37") (pin "1") (pinfunction "1_1") (pintype "passive"))
      (node (ref "S5") (pin "1") (pinfunction "LO_1") (pintype "passive"))
    )
    (net (code "34") (name "Net-(D23-A)") (class "Default")
      (node (ref "D23") (pin "1") (pinfunction "A_1") (pintype "passive"))
      (node (ref "Q13") (pin "1") (pinfunction "G_1") (pintype "passive"))
      (node (ref "R37") (pin "2") (pinfunction "2_2") (pintype "passive"))
    )
    (net (code "35") (name "Net-(D24-A)") (class "Default")
      (node (ref "C44") (pin "2") (pinfunction "2_2") (pintype "passive"))
      (node (ref "D24") (pin "1") (pinfunction "A_1") (pintype "passive"))
      (node (ref "R38") (pin "2") (pinfunction "2_2") (pintype "passive"))
    )
    (net (code "36") (name "Net-(IC-(ADC0)PC0)") (class "Default")
      (node (ref "C12") (pin "1") (pinfunction "1_1") (pintype "passive"))
      (node (ref "IC") (pin "23") (pinfunction "(ADC0)PC0_23") (pintype "bidirectional"))
      (node (ref "U") (pin "3") (pinfunction "VIOUT_3") (pintype "output"))
    )
    (net (code "37") (name "Net-(IC-(ADC1)PC1)") (class "Default")
      (node (ref "IC") (pin "24") (pinfunction "(ADC1)PC1_24") (pintype "bidirectional"))
      (node (ref "R4") (pin "1") (pinfunction "1_1") (pintype "passive"))
    )
    (net (code "38") (name "Net-(IC-(ADC2)PC2)") (class "Default")
      (node (ref "IC") (pin "25") (pinfunction "(ADC2)PC2_25") (pintype "bidirectional"))
      (node (ref "P5") (pin "1") (pinfunction "1_1") (pintype "passive"))
    )
    (net (code "39") (name "Net-(IC-(ADC3)PC3)") (class "Default")
      (node (ref "IC") (pin "26") (pinfunction "(ADC3)PC3_26") (pintype "bidirectional"))
      (node (ref "P5") (pin "2") (pinfunction "2_2") (pintype "passive"))
    )
    (net (code "40") (name "Net-(IC-(AIN1)PD7)") (class "Default")
      (node (ref "IC") (pin "13") (pinfunction "(AIN1)PD7_13") (pintype "bidirectional"))
      (node (ref "S3") (pin "18") (pinfunction "CW/CCW_18") (pintype "passive"))
    )
    (net (code "41") (name "Net-(IC-(CLKO{slash}ICP1)PB0)") (class "Default")
      (node (ref "IC") (pin "14") (pinfunction "(CLKO/ICP1)PB0_14") (pintype "bidirectional"))
      (node (ref "R8") (pin "2") (pinfunction "2_2") (pintype "passive"))
      (node (ref "S3") (pin "11") (pinfunction "RES_11") (pintype "passive"))
    )
    (net (code "42") (name "Net-(IC-(MISO)PB4)") (class "Default")
      (node (ref "IC") (pin "18") (pinfunction "(MISO)PB4_18") (pintype "bidirectional"))
      (node (ref "P2") (pin "4") (pinfunction "SO_4") (pintype "passive"))
    )
    (net (code "43") (name "Net-(IC-(OC0A{slash}AIN0)PD6)") (class "Default")
      (node (ref "IC") (pin "12") (pinfunction "(OC0A/AIN0)PD6_12") (pintype "bidirectional"))
      (node (ref "R17") (pin "1") (pinfunction "1_1") (pintype "passive"))
    )
    (net (code "44") (name "Net-(IC-(OC0B{slash}T1)PD5)") (class "Default")
      (node (ref "IC") (pin "11") (pinfunction "(OC0B/T1)PD5_11") (pintype "bidirectional"))
      (node (ref "R14") (pin "1") (pinfunction "1_1") (pintype "passive"))
    )
    (net (code "45") (name "Net-(IC-(OC2A{slash}MOSI)PB3)") (class "Default")
      (node (ref "IC") (pin "17") (pinfunction "(OC2A/MOSI)PB3_17") (pintype "bidirectional"))
      (node (ref "P2") (pin "3") (pinfunction "SI_3") (pintype "passive"))
    )
    (net (code "46") (name "Net-(IC-(RXD)PD0)") (class "Default")
      (node (ref "IC") (pin "2") (pinfunction "(RXD)PD0_2") (pintype "bidirectional"))
      (node (ref "P3") (pin "2") (pinfunction "Rx_2") (pintype "passive"))
    )
    (net (code "47") (name "Net-(IC-(SCK)PB5)") (class "Default")
      (node (ref "IC") (pin "19") (pinfunction "(SCK)PB5_19") (pintype "bidirectional"))
      (node (ref "P2") (pin "2") (pinfunction "SCK_2") (pintype "passive"))
    )
    (net (code "48") (name "Net-(IC-(SCL{slash}ADC5)PC5)") (class "Default")
      (node (ref "IC") (pin "28") (pinfunction "(SCL/ADC5)PC5_28") (pintype "bidirectional"))
      (node (ref "P5") (pin "4") (pinfunction "4_4") (pintype "passive"))
    )
    (net (code "49") (name "Net-(IC-(SDA{slash}ADC4)PC4)") (class "Default")
      (node (ref "IC") (pin "27") (pinfunction "(SDA/ADC4)PC4_27") (pintype "bidirectional"))
      (node (ref "P5") (pin "3") (pinfunction "3_3") (pintype "passive"))
    )
    (net (code "50") (name "Net-(IC-(SS{slash}OC1B)PB2)") (class "Default")
      (node (ref "IC") (pin "16") (pinfunction "(SS/OC1B)PB2_16") (pintype "bidirectional"))
      (node (ref "P2") (pin "5") (pinfunction "CS_5") (pintype "passive"))
    )
    (net (code "51") (name "Net-(IC-(TXD)PD1)") (class "Default")
      (node (ref "IC") (pin "3") (pinfunction "(TXD)PD1_3") (pintype "bidirectional"))
      (node (ref "P3") (pin "1") (pinfunction "Tx_1") (pintype "passive"))
    )
    (net (code "52") (name "Net-(IC-(XCK{slash}T0)PD4)") (class "Default")
      (node (ref "IC") (pin "6") (pinfunction "(XCK/T0)PD4_6") (pintype "bidirectional"))
      (node (ref "R18") (pin "1") (pinfunction "1_1") (pintype "passive"))
      (node (ref "S3") (pin "10") (pinfunction "Td_10") (pintype "passive"))
    )
    (net (code "53") (name "Net-(IC-PB6(XTAL1))") (class "Default")
      (node (ref "C18") (pin "1") (pinfunction "1_1") (pintype "passive"))
      (node (ref "IC") (pin "9") (pinfunction "PB6(XTAL1)_9") (pintype "bidirectional"))
      (node (ref "Y1") (pin "2") (pinfunction "OSC2_2") (pintype "passive"))
    )
    (net (code "54") (name "Net-(IC-PB7(XTAL2))") (class "Default")
      (node (ref "C19") (pin "1") (pinfunction "1_1") (pintype "passive"))
      (node (ref "IC") (pin "10") (pinfunction "PB7(XTAL2)_10") (pintype "bidirectional"))
      (node (ref "Y1") (pin "1") (pinfunction "OSC1_1") (pintype "passive"))
    )
    (net (code "55") (name "Net-(IC-PC6(!RESET!))") (class "Default")
      (node (ref "IC") (pin "1") (pinfunction "PC6(!RESET!)_1") (pintype "bidirectional"))
      (node (ref "R2") (pin "1") (pinfunction "1_1") (pintype "passive"))
      (node (ref "S1") (pin "2") (pinfunction "NO_2") (pintype "passive"))
    )
    (net (code "56") (name "Net-(P4-HU)") (class "Default")
      (node (ref "P4") (pin "3") (pinfunction "HU_3") (pintype "passive"))
      (node (ref "R26") (pin "1") (pinfunction "1_1") (pintype "passive"))
      (node (ref "R32") (pin "1") (pinfunction "1_1") (pintype "passive"))
    )
    (net (code "57") (name "Net-(P4-HV)") (class "Default")
      (node (ref "P4") (pin "4") (pinfunction "HV_4") (pintype "passive"))
      (node (ref "R27") (pin "1") (pinfunction "1_1") (pintype "passive"))
      (node (ref "R31") (pin "1") (pinfunction "1_1") (pintype "passive"))
    )
    (net (code "58") (name "Net-(P4-HW)") (class "Default")
      (node (ref "P4") (pin "5") (pinfunction "HW_5") (pintype "passive"))
      (node (ref "R28") (pin "1") (pinfunction "1_1") (pintype "passive"))
      (node (ref "R30") (pin "1") (pinfunction "1_1") (pintype "passive"))
    )
    (net (code "59") (name "Net-(Q1-B)") (class "Default")
      (node (ref "Q1") (pin "2") (pinfunction "B_2") (pintype "passive"))
      (node (ref "R4") (pin "2") (pinfunction "2_2") (pintype "passive"))
    )
    (net (code "60") (name "Net-(Q1-C)") (class "Default")
      (node (ref "LS") (pin "M") (pinfunction "M_M") (pintype "passive"))
      (node (ref "Q1") (pin "1") (pinfunction "C_1") (pintype "passive"))
    )
    (net (code "61") (name "Net-(Q10-D)") (class "Default")
      (node (ref "C10") (pin "1") (pinfunction "1_1") (pintype "passive"))
      (node (ref "C11") (pin "1") (pinfunction "1_1") (pintype "passive"))
      (node (ref "C15") (pin "1") (pinfunction "1_1") (pintype "passive"))
      (node (ref "C26") (pin "1") (pinfunction "1_1") (pintype "passive"))
      (node (ref "C37") (pin "1") (pinfunction "1_1") (pintype "passive"))
      (node (ref "C8") (pin "1") (pinfunction "1_1") (pintype "passive"))
      (node (ref "C9") (pin "1") (pinfunction "1_1") (pintype "passive"))
      (node (ref "Q10") (pin "2") (pinfunction "D_2") (pintype "passive"))
      (node (ref "Q11") (pin "2") (pinfunction "D_2") (pintype "passive"))
      (node (ref "Q2") (pin "2") (pinfunction "D_2") (pintype "passive"))
      (node (ref "Q3") (pin "2") (pinfunction "D_2") (pintype "passive"))
      (node (ref "Q6") (pin "2") (pinfunction "D_2") (pintype "passive"))
      (node (ref "Q7") (pin "2") (pinfunction "D_2") (pintype "passive"))
      (node (ref "U") (pin "5") (pinfunction "IP-_5") (pintype "bidirectional"))
    )
    (net (code "62") (name "Net-(S2-Hin)") (class "Default")
      (node (ref "S2") (pin "10") (pinfunction "Hin_10") (pintype "passive"))
      (node (ref "S3") (pin "9") (pinfunction "U_9") (pintype "passive"))
    )
    (net (code "63") (name "Net-(S2-Lin)") (class "Default")
      (node (ref "S2") (pin "12") (pinfunction "Lin_12") (pintype "passive"))
      (node (ref "S3") (pin "6") (pinfunction "X_6") (pintype "passive"))
    )
    (net (code "64") (name "Net-(S2-SD)") (class "Default")
      (node (ref "R39") (pin "2") (pinfunction "2_2") (pintype "passive"))
      (node (ref "S2") (pin "11") (pinfunction "SD_11") (pintype "passive"))
      (node (ref "S4") (pin "11") (pinfunction "SD_11") (pintype "passive"))
      (node (ref "S5") (pin "11") (pinfunction "SD_11") (pintype "passive"))
    )
    (net (code "65") (name "Net-(S2-Vb)") (class "Default")
      (node (ref "C16") (pin "1") (pinfunction "1_1") (pintype "passive"))
      (node (ref "R3") (pin "2") (pinfunction "2_2") (pintype "passive"))
      (node (ref "S2") (pin "6") (pinfunction "Vb_6") (pintype "passive"))
    )
    (net (code "66") (name "Net-(S3-HU)") (class "Default")
      (node (ref "C38") (pin "1") (pinfunction "1_1") (pintype "passive"))
      (node (ref "R32") (pin "2") (pinfunction "2_2") (pintype "passive"))
      (node (ref "S3") (pin "21") (pinfunction "HU_21") (pintype "passive"))
    )
    (net (code "67") (name "Net-(S3-HV)") (class "Default")
      (node (ref "C39") (pin "1") (pinfunction "1_1") (pintype "passive"))
      (node (ref "R31") (pin "2") (pinfunction "2_2") (pintype "passive"))
      (node (ref "S3") (pin "20") (pinfunction "HV_20") (pintype "passive"))
    )
    (net (code "68") (name "Net-(S3-HW)") (class "Default")
      (node (ref "C40") (pin "1") (pinfunction "1_1") (pintype "passive"))
      (node (ref "R30") (pin "2") (pinfunction "2_2") (pintype "passive"))
      (node (ref "S3") (pin "19") (pinfunction "HW_19") (pintype "passive"))
    )
    (net (code "69") (name "Net-(S3-LA)") (class "Default")
      (node (ref "C30") (pin "1") (pinfunction "1_1") (pintype "passive"))
      (node (ref "R17") (pin "2") (pinfunction "2_2") (pintype "passive"))
      (node (ref "R22") (pin "2") (pinfunction "2_2") (pintype "passive"))
      (node (ref "S3") (pin "23") (pinfunction "LA_23") (pintype "passive"))
    )
    (net (code "70") (name "Net-(S3-OS)") (class "Default")
      (node (ref "C36") (pin "1") (pinfunction "1_1") (pintype "passive"))
      (node (ref "R18") (pin "2") (pinfunction "2_2") (pintype "passive"))
      (node (ref "S3") (pin "12") (pinfunction "OS_12") (pintype "passive"))
      (node (ref "S3") (pin "24") (pinfunction "Vrefout_24") (pintype "passive"))
    )
    (net (code "71") (name "Net-(S3-V)") (class "Default")
      (node (ref "S3") (pin "8") (pinfunction "V_8") (pintype "passive"))
      (node (ref "S4") (pin "10") (pinfunction "Hin_10") (pintype "passive"))
    )
    (net (code "72") (name "Net-(S3-Vcc)") (class "Default")
      (node (ref "C35") (pin "1") (pinfunction "1_1") (pintype "passive"))
      (node (ref "S3") (pin "1") (pinfunction "Vcc_1") (pintype "passive"))
    )
    (net (code "73") (name "Net-(S3-Ve)") (class "Default")
      (node (ref "C25") (pin "1") (pinfunction "1_1") (pintype "passive"))
      (node (ref "R14") (pin "2") (pinfunction "2_2") (pintype "passive"))
      (node (ref "R15") (pin "2") (pinfunction "2_2") (pintype "passive"))
      (node (ref "S3") (pin "22") (pinfunction "Ve_22") (pintype "passive"))
    )
    (net (code "74") (name "Net-(S3-W)") (class "Default")
      (node (ref "S3") (pin "7") (pinfunction "W_7") (pintype "passive"))
      (node (ref "S5") (pin "10") (pinfunction "Hin_10") (pintype "passive"))
    )
    (net (code "75") (name "Net-(S3-Xin)") (class "Default")
      (node (ref "C31") (pin "1") (pinfunction "1_1") (pintype "passive"))
      (node (ref "S3") (pin "14") (pinfunction "Xin_14") (pintype "passive"))
      (node (ref "Y2") (pin "2") (pinfunction "OSC2_2") (pintype "passive"))
    )
    (net (code "76") (name "Net-(S3-Xout)") (class "Default")
      (node (ref "C29") (pin "1") (pinfunction "1_1") (pintype "passive"))
      (node (ref "S3") (pin "15") (pinfunction "Xout_15") (pintype "passive"))
      (node (ref "Y2") (pin "1") (pinfunction "OSC1_1") (pintype "passive"))
    )
    (net (code "77") (name "Net-(S3-Y)") (class "Default")
      (node (ref "S3") (pin "5") (pinfunction "Y_5") (pintype "passive"))
      (node (ref "S4") (pin "12") (pinfunction "Lin_12") (pintype "passive"))
    )
    (net (code "78") (name "Net-(S3-Z)") (class "Default")
      (node (ref "S3") (pin "4") (pinfunction "Z_4") (pintype "passive"))
      (node (ref "S5") (pin "12") (pinfunction "Lin_12") (pintype "passive"))
    )
    (net (code "79") (name "Net-(S4-Vb)") (class "Default")
      (node (ref "C27") (pin "1") (pinfunction "1_1") (pintype "passive"))
      (node (ref "R16") (pin "2") (pinfunction "2_2") (pintype "passive"))
      (node (ref "S4") (pin "6") (pinfunction "Vb_6") (pintype "passive"))
    )
    (net (code "80") (name "Net-(S5-Vb)") (class "Default")
      (node (ref "C42") (pin "1") (pinfunction "1_1") (pintype "passive"))
      (node (ref "R29") (pin "1") (pinfunction "1_1") (pintype "passive"))
      (node (ref "S5") (pin "6") (pinfunction "Vb_6") (pintype "passive"))
    )
    (net (code "81") (name "Net-(VR1-Vin)") (class "Default")
      (node (ref "VR1") (pin "1") (pinfunction "Vin_1") (pintype "passive"))
      (node (ref "VR2") (pin "4") (pinfunction "Vout_4") (pintype "passive"))
    )
    (net (code "82") (name "Net-(VR3-Vout)") (class "Default")
      (node (ref "P1") (pin "5") (pinfunction "SW_5") (pintype "passive"))
      (node (ref "VR3") (pin "3") (pinfunction "Vout_3") (pintype "passive"))
    )
    (net (code "83") (name "Net-(VR4-Vin)") (class "Default")
      (node (ref "C3") (pin "1") (pinfunction "1_1") (pintype "passive"))
      (node (ref "P1") (pin "6") (pinfunction "SW_6") (pintype "passive"))
      (node (ref "VR4") (pin "1") (pinfunction "Vin_1") (pintype "passive"))
    )
    (net (code "84") (name "PGND") (class "Default")
      (node (ref "C1") (pin "2") (pinfunction "2_2") (pintype "passive"))
      (node (ref "C10") (pin "2") (pinfunction "2_2") (pintype "passive"))
      (node (ref "C11") (pin "2") (pinfunction "2_2") (pintype "passive"))
      (node (ref "C2") (pin "2") (pinfunction "2_2") (pintype "passive"))
      (node (ref "C21") (pin "2") (pinfunction "2_2") (pintype "passive"))
      (node (ref "C22") (pin "2") (pinfunction "2_2") (pintype "passive"))
      (node (ref "C33") (pin "2") (pinfunction "2_2") (pintype "passive"))
      (node (ref "C34") (pin "2") (pinfunction "2_2") (pintype "passive"))
      (node (ref "C45") (pin "2") (pinfunction "2_2") (pintype "passive"))
      (node (ref "C46") (pin "2") (pinfunction "2_2") (pintype "passive"))
      (node (ref "C8") (pin "2") (pinfunction "2_2") (pintype "passive"))
      (node (ref "C9") (pin "2") (pinfunction "2_2") (pintype "passive"))
      (node (ref "D17") (pin "2") (pinfunction "K_2") (pintype "passive"))
      (node (ref "D24") (pin "2") (pinfunction "K_2") (pintype "passive"))
      (node (ref "D8") (pin "2") (pinfunction "K_2") (pintype "passive"))
      (node (ref "J2") (pin "1") (pinfunction "1_1") (pintype "passive"))
      (node (ref "Q12") (pin "3") (pinfunction "S_3") (pintype "passive"))
      (node (ref "Q13") (pin "3") (pinfunction "S_3") (pintype "passive"))
      (node (ref "Q4") (pin "3") (pinfunction "S_3") (pintype "passive"))
      (node (ref "Q5") (pin "3") (pinfunction "S_3") (pintype "passive"))
      (node (ref "Q8") (pin "3") (pinfunction "S_3") (pintype "passive"))
      (node (ref "Q9") (pin "3") (pinfunction "S_3") (pintype "passive"))
      (node (ref "R11") (pin "1") (pinfunction "1_1") (pintype "passive"))
      (node (ref "R25") (pin "1") (pinfunction "1_1") (pintype "passive"))
      (node (ref "R38") (pin "1") (pinfunction "1_1") (pintype "passive"))
      (node (ref "S2") (pin "2") (pinfunction "COM_2") (pintype "passive"))
      (node (ref "S4") (pin "2") (pinfunction "COM_2") (pintype "passive"))
      (node (ref "S5") (pin "2") (pinfunction "COM_2") (pintype "passive"))
      (node (ref "VR1") (pin "2") (pinfunction "GND_2") (pintype "passive"))
      (node (ref "VR2") (pin "1") (pinfunction "Vin-_1") (pintype "passive"))
      (node (ref "VR2") (pin "3") (pinfunction "Gnd_3") (pintype "passive"))
      (node (ref "VR3") (pin "2") (pinfunction "Vin-_2") (pintype "passive"))
    )
    (net (code "85") (name "S-GND") (class "Default")
      (node (ref "C12") (pin "2") (pinfunction "2_2") (pintype "passive"))
      (node (ref "C13") (pin "2") (pinfunction "2_2") (pintype "passive"))
      (node (ref "C14") (pin "2") (pinfunction "2_2") (pintype "passive"))
      (node (ref "C17") (pin "2") (pinfunction "2_2") (pintype "passive"))
      (node (ref "C18") (pin "2") (pinfunction "2_2") (pintype "passive"))
      (node (ref "C19") (pin "2") (pinfunction "2_2") (pintype "passive"))
      (node (ref "C23") (pin "2") (pinfunction "2_2") (pintype "passive"))
      (node (ref "C24") (pin "2") (pinfunction "2_2") (pintype "passive"))
      (node (ref "C25") (pin "2") (pinfunction "2_2") (pintype "passive"))
      (node (ref "C28") (pin "2") (pinfunction "2_2") (pintype "passive"))
      (node (ref "C29") (pin "2") (pinfunction "2_2") (pintype "passive"))
      (node (ref "C3") (pin "2") (pinfunction "2_2") (pintype "passive"))
      (node (ref "C30") (pin "2") (pinfunction "2_2") (pintype "passive"))
      (node (ref "C31") (pin "2") (pinfunction "2_2") (pintype "passive"))
      (node (ref "C35") (pin "2") (pinfunction "2_2") (pintype "passive"))
      (node (ref "C36") (pin "2") (pinfunction "2_2") (pintype "passive"))
      (node (ref "C38") (pin "2") (pinfunction "2_2") (pintype "passive"))
      (node (ref "C39") (pin "2") (pinfunction "2_2") (pintype "passive"))
      (node (ref "C4") (pin "2") (pinfunction "2_2") (pintype "passive"))
      (node (ref "C40") (pin "2") (pinfunction "2_2") (pintype "passive"))
      (node (ref "C41") (pin "2") (pinfunction "2_2") (pintype "passive"))
      (node (ref "C43") (pin "2") (pinfunction "2_2") (pintype "passive"))
      (node (ref "C5") (pin "2") (pinfunction "2_2") (pintype "passive"))
      (node (ref "C6") (pin "2") (pinfunction "2_2") (pintype "passive"))
      (node (ref "C7") (pin "2") (pinfunction "2_2") (pintype "passive"))
      (node (ref "IC") (pin "22") (pinfunction "GND_22") (pintype "power_in"))
      (node (ref "IC") (pin "8") (pinfunction "GND_8") (pintype "power_in"))
      (node (ref "P1") (pin "2") (pinfunction "SGND_2") (pintype "passive"))
      (node (ref "P2") (pin "6") (pinfunction "Gnd_6") (pintype "passive"))
      (node (ref "P3") (pin "3") (pinfunction "Gnd_3") (pintype "passive"))
      (node (ref "P4") (pin "2") (pinfunction "Gnd_2") (pintype "passive"))
      (node (ref "Q1") (pin "3") (pinfunction "E_3") (pintype "passive"))
      (node (ref "R1") (pin "2") (pinfunction "2_2") (pintype "passive"))
      (node (ref "R12") (pin "2") (pinfunction "2_2") (pintype "passive"))
      (node (ref "R13") (pin "2") (pinfunction "2_2") (pintype "passive"))
      (node (ref "R15") (pin "1") (pinfunction "1_1") (pintype "passive"))
      (node (ref "R22") (pin "1") (pinfunction "1_1") (pintype "passive"))
      (node (ref "R39") (pin "1") (pinfunction "1_1") (pintype "passive"))
      (node (ref "R8") (pin "1") (pinfunction "1_1") (pintype "passive"))
      (node (ref "S1") (pin "1") (pinfunction "COMMON_1") (pintype "passive"))
      (node (ref "S2") (pin "13") (pinfunction "Vss_13") (pintype "passive"))
      (node (ref "S3") (pin "13") (pinfunction "S-Gnd_13") (pintype "passive"))
      (node (ref "S3") (pin "2") (pinfunction "P-Gnd_2") (pintype "passive"))
      (node (ref "S3") (pin "3") (pinfunction "Idc_3") (pintype "passive"))
      (node (ref "S4") (pin "13") (pinfunction "Vss_13") (pintype "passive"))
      (node (ref "S5") (pin "13") (pinfunction "Vss_13") (pintype "passive"))
      (node (ref "U") (pin "2") (pinfunction "GND_2") (pintype "power_in"))
      (node (ref "VR3") (pin "4") (pinfunction "GND_4") (pintype "passive"))
      (node (ref "VR4") (pin "2") (pinfunction "GND_2") (pintype "passive"))
      (node (ref "VR5") (pin "2") (pinfunction "GND_2") (pintype "passive"))
    )
    (net (code "86") (name "VCC-5") (class "Default")
      (node (ref "C13") (pin "1") (pinfunction "1_1") (pintype "passive"))
      (node (ref "C14") (pin "1") (pinfunction "1_1") (pintype "passive"))
      (node (ref "C23") (pin "1") (pinfunction "1_1") (pintype "passive"))
      (node (ref "C24") (pin "1") (pinfunction "1_1") (pintype "passive"))
      (node (ref "C43") (pin "1") (pinfunction "1_1") (pintype "passive"))
      (node (ref "C6") (pin "1") (pinfunction "1_1") (pintype "passive"))
      (node (ref "C7") (pin "1") (pinfunction "1_1") (pintype "passive"))
      (node (ref "D1") (pin "1") (pinfunction "A_1") (pintype "passive"))
      (node (ref "IC") (pin "20") (pinfunction "AVCC_20") (pintype "power_in"))
      (node (ref "IC") (pin "21") (pinfunction "AREF_21") (pintype "passive"))
      (node (ref "IC") (pin "7") (pinfunction "VCC_7") (pintype "power_in"))
      (node (ref "LS") (pin "P") (pinfunction "P_P") (pintype "passive"))
      (node (ref "P1") (pin "1") (pinfunction "5V_1") (pintype "passive"))
      (node (ref "P2") (pin "7") (pinfunction "Vcc_7") (pintype "passive"))
      (node (ref "P4") (pin "1") (pinfunction "Vcc-5v_1") (pintype "passive"))
      (node (ref "R2") (pin "2") (pinfunction "2_2") (pintype "passive"))
      (node (ref "R26") (pin "2") (pinfunction "2_2") (pintype "passive"))
      (node (ref "R27") (pin "2") (pinfunction "2_2") (pintype "passive"))
      (node (ref "R28") (pin "2") (pinfunction "2_2") (pintype "passive"))
      (node (ref "U") (pin "1") (pinfunction "VCC_1") (pintype "power_in"))
      (node (ref "VR5") (pin "3") (pinfunction "Vout_3") (pintype "passive"))
    )
    (net (code "87") (name "VCC-9") (class "Default")
      (node (ref "C17") (pin "1") (pinfunction "1_1") (pintype "passive"))
      (node (ref "C28") (pin "1") (pinfunction "1_1") (pintype "passive"))
      (node (ref "C4") (pin "1") (pinfunction "1_1") (pintype "passive"))
      (node (ref "C41") (pin "1") (pinfunction "1_1") (pintype "passive"))
      (node (ref "C5") (pin "1") (pinfunction "1_1") (pintype "passive"))
      (node (ref "S2") (pin "9") (pinfunction "Vdd_9") (pintype "passive"))
      (node (ref "S4") (pin "9") (pinfunction "Vdd_9") (pintype "passive"))
      (node (ref "S5") (pin "9") (pinfunction "Vdd_9") (pintype "passive"))
      (node (ref "VR4") (pin "3") (pinfunction "Vout_3") (pintype "passive"))
      (node (ref "VR5") (pin "1") (pinfunction "Vin_1") (pintype "passive"))
    )
    (net (code "88") (name "VCC-12") (class "Default")
      (node (ref "C1") (pin "1") (pinfunction "1_1") (pintype "passive"))
      (node (ref "C2") (pin "1") (pinfunction "1_1") (pintype "passive"))
      (node (ref "C21") (pin "1") (pinfunction "1_1") (pintype "passive"))
      (node (ref "C22") (pin "1") (pinfunction "1_1") (pintype "passive"))
      (node (ref "C33") (pin "1") (pinfunction "1_1") (pintype "passive"))
      (node (ref "C34") (pin "1") (pinfunction "1_1") (pintype "passive"))
      (node (ref "C45") (pin "1") (pinfunction "1_1") (pintype "passive"))
      (node (ref "C46") (pin "1") (pinfunction "1_1") (pintype "passive"))
      (node (ref "D11") (pin "1") (pinfunction "A_1") (pintype "passive"))
      (node (ref "D18") (pin "1") (pinfunction "A_1") (pintype "passive"))
      (node (ref "D2") (pin "1") (pinfunction "A_1") (pintype "passive"))
      (node (ref "S2") (pin "3") (pinfunction "Vcc_3") (pintype "passive"))
      (node (ref "S4") (pin "3") (pinfunction "Vcc_3") (pintype "passive"))
      (node (ref "S5") (pin "3") (pinfunction "Vcc_3") (pintype "passive"))
      (node (ref "VR1") (pin "3") (pinfunction "Vout_3") (pintype "passive"))
    )
    (net (code "89") (name "VCC-48") (class "Default")
      (node (ref "J1") (pin "1") (pinfunction "1_1") (pintype "passive"))
      (node (ref "U") (pin "4") (pinfunction "IP+_4") (pintype "bidirectional"))
      (node (ref "VR2") (pin "2") (pinfunction "Vin+_2") (pintype "passive"))
      (node (ref "VR3") (pin "1") (pinfunction "Vin+_1") (pintype "passive"))
    )
    (net (code "90") (name "unconnected-(IC-(OC1A)PB1-Pad15)") (class "Default")
      (node (ref "IC") (pin "15") (pinfunction "(OC1A)PB1_15") (pintype "bidirectional"))
    )
    (net (code "91") (name "unconnected-(P1-SRC+-Pad3)") (class "Default")
      (node (ref "P1") (pin "3") (pinfunction "SRC+_3") (pintype "passive"))
    )
    (net (code "92") (name "unconnected-(P1-SRC--Pad4)") (class "Default")
      (node (ref "P1") (pin "4") (pinfunction "SRC-_4") (pintype "passive"))
    )
    (net (code "93") (name "unconnected-(P2-INT-Pad1)") (class "Default")
      (node (ref "P2") (pin "1") (pinfunction "INT_1") (pintype "passive"))
    )
    (net (code "94") (name "unconnected-(P3-Vcc-Pad4)") (class "Default")
      (node (ref "P3") (pin "4") (pinfunction "Vcc_4") (pintype "passive"))
    )
    (net (code "95") (name "unconnected-(S2-NC-Pad4)") (class "Default")
      (node (ref "S2") (pin "4") (pinfunction "NC_4") (pintype "passive"))
    )
    (net (code "96") (name "unconnected-(S2-NC-Pad8)") (class "Default")
      (node (ref "S2") (pin "8") (pinfunction "NC_8") (pintype "passive"))
    )
    (net (code "97") (name "unconnected-(S2-NC-Pad14)") (class "Default")
      (node (ref "S2") (pin "14") (pinfunction "NC_14") (pintype "passive"))
    )
    (net (code "98") (name "unconnected-(S4-NC-Pad4)") (class "Default")
      (node (ref "S4") (pin "4") (pinfunction "NC_4") (pintype "passive"))
    )
    (net (code "99") (name "unconnected-(S4-NC-Pad8)") (class "Default")
      (node (ref "S4") (pin "8") (pinfunction "NC_8") (pintype "passive"))
    )
    (net (code "100") (name "unconnected-(S4-NC-Pad14)") (class "Default")
      (node (ref "S4") (pin "14") (pinfunction "NC_14") (pintype "passive"))
    )
    (net (code "101") (name "unconnected-(S5-NC-Pad4)") (class "Default")
      (node (ref "S5") (pin "4") (pinfunction "NC_4") (pintype "passive"))
    )
    (net (code "102") (name "unconnected-(S5-NC-Pad8)") (class "Default")
      (node (ref "S5") (pin "8") (pinfunction "NC_8") (pintype "passive"))
    )
    (net (code "103") (name "unconnected-(S5-NC-Pad14)") (class "Default")
      (node (ref "S5") (pin "14") (pinfunction "NC_14") (pintype "passive"))
    )
  )
)
